# WL-ATT.net
KiCad netlist of a schematic drawn in Altium Designer
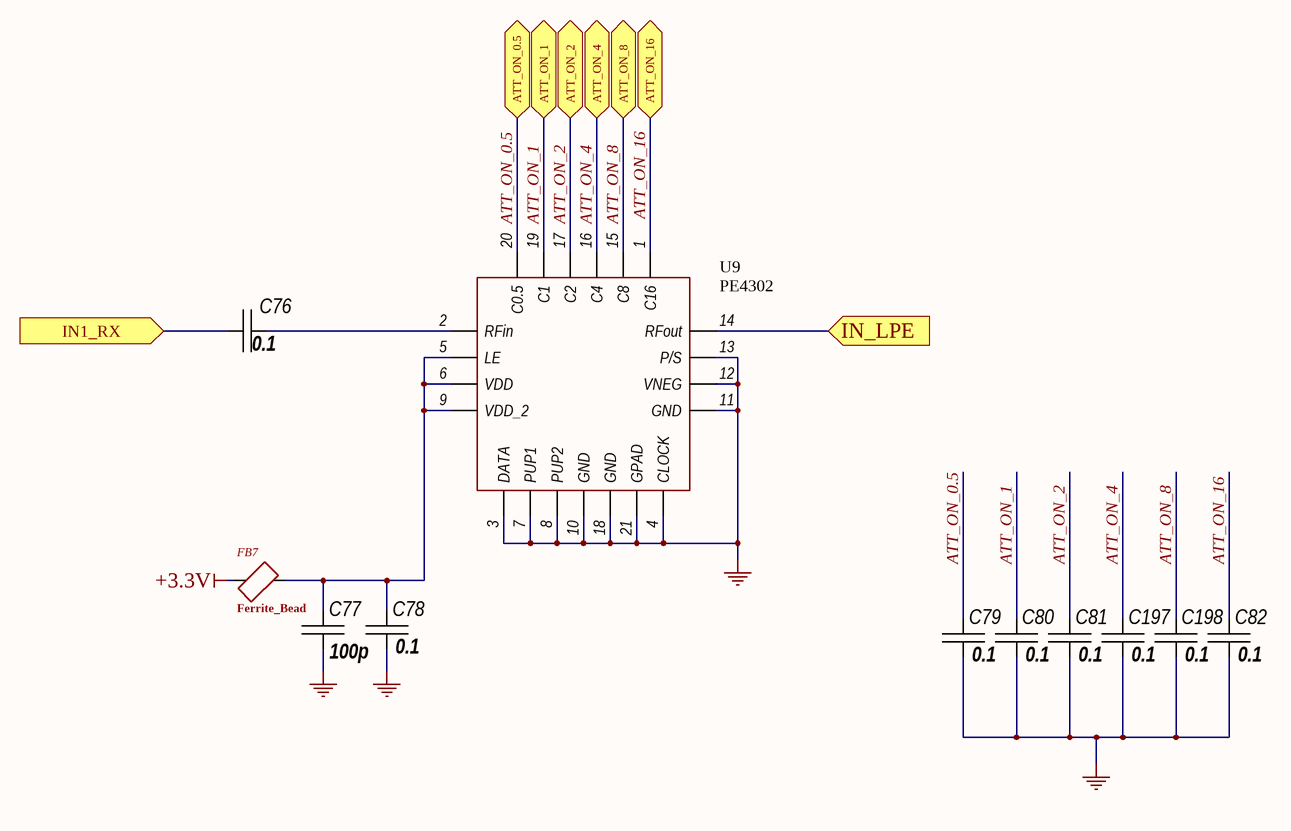
[diagram p0: WL-ATT.SchDoc]

(export (version "E")
  (design (tool "Eeschema 10.0.6"))
  (components
    (comp (ref "C76")
      (value "0.1")
      (footprint "standard:CH0805C")
      (libsource (lib "Discrete") (part "Capacitor"))
    )
    (comp (ref "C77")
      (value "100p")
      (footprint "standard:CH0805C")
      (libsource (lib "Discrete") (part "Capacitor"))
    )
    (comp (ref "C78")
      (value "0.1")
      (footprint "standard:CH0805C")
      (libsource (lib "Discrete") (part "Capacitor"))
    )
    (comp (ref "C79")
      (value "0.1")
      (footprint "standard:CH0805C")
      (libsource (lib "Discrete") (part "Capacitor"))
    )
    (comp (ref "C80")
      (value "0.1")
      (footprint "standard:CH0805C")
      (libsource (lib "Discrete") (part "Capacitor"))
    )
    (comp (ref "C81")
      (value "0.1")
      (footprint "standard:CH0805C")
      (libsource (lib "Discrete") (part "Capacitor"))
    )
    (comp (ref "C82")
      (value "0.1")
      (footprint "standard:CH0805C")
      (libsource (lib "Discrete") (part "Capacitor"))
    )
    (comp (ref "C197")
      (value "0.1")
      (footprint "standard:CH0805C")
      (libsource (lib "Discrete") (part "Capacitor"))
    )
    (comp (ref "C198")
      (value "0.1")
      (footprint "standard:CH0805C")
      (libsource (lib "Discrete") (part "Capacitor"))
    )
    (comp (ref "FB7") (value "Ferrite_Bead") (footprint "CH0805L") (libsource (lib "Discrete") (part "FB")))
    (comp (ref "U9") (value "PE4302") (footprint "20-QFN (4x4)") (libsource (lib "Digital") (part "PE4302")))
  )
  (nets
    (net (code "1") (name "+3.3V") (class "Default")
      (node (ref "FB7") (pin "2") (pinfunction "2_2") (pintype "passive"))
    )
    (net (code "2") (name "/ATT_ON_0.5") (class "Default")
      (node (ref "C79") (pin "2") (pinfunction "2_2") (pintype "power_in"))
      (node (ref "U9") (pin "20") (pinfunction "C0.5_20") (pintype "passive"))
    )
    (net (code "3") (name "/ATT_ON_1") (class "Default")
      (node (ref "C80") (pin "2") (pinfunction "2_2") (pintype "power_in"))
      (node (ref "U9") (pin "19") (pinfunction "C1_19") (pintype "passive"))
    )
    (net (code "4") (name "/ATT_ON_2") (class "Default")
      (node (ref "C81") (pin "2") (pinfunction "2_2") (pintype "power_in"))
      (node (ref "U9") (pin "17") (pinfunction "C2_17") (pintype "passive"))
    )
    (net (code "5") (name "/ATT_ON_4") (class "Default")
      (node (ref "C197") (pin "2") (pinfunction "2_2") (pintype "power_in"))
      (node (ref "U9") (pin "16") (pinfunction "C4_16") (pintype "passive"))
    )
    (net (code "6") (name "/ATT_ON_8") (class "Default")
      (node (ref "C198") (pin "2") (pinfunction "2_2") (pintype "power_in"))
      (node (ref "U9") (pin "15") (pinfunction "C8_15") (pintype "passive"))
    )
    (net (code "7") (name "/ATT_ON_16") (class "Default")
      (node (ref "C82") (pin "2") (pinfunction "2_2") (pintype "power_in"))
      (node (ref "U9") (pin "1") (pinfunction "C16_1") (pintype "passive"))
    )
    (net (code "8") (name "/IN1_RX") (class "Default")
      (node (ref "C76") (pin "1") (pinfunction "1_1") (pintype "power_in"))
    )
    (net (code "9") (name "/IN_LPE") (class "Default")
      (node (ref "U9") (pin "14") (pinfunction "RFout_14") (pintype "passive"))
    )
    (net (code "10") (name "GND") (class "Default")
      (node (ref "C197") (pin "1") (pinfunction "1_1") (pintype "power_in"))
      (node (ref "C198") (pin "1") (pinfunction "1_1") (pintype "power_in"))
      (node (ref "C77") (pin "1") (pinfunction "1_1") (pintype "power_in"))
      (node (ref "C78") (pin "1") (pinfunction "1_1") (pintype "power_in"))
      (node (ref "C79") (pin "1") (pinfunction "1_1") (pintype "power_in"))
      (node (ref "C80") (pin "1") (pinfunction "1_1") (pintype "power_in"))
      (node (ref "C81") (pin "1") (pinfunction "1_1") (pintype "power_in"))
      (node (ref "C82") (pin "1") (pinfunction "1_1") (pintype "power_in"))
      (node (ref "U9") (pin "10") (pinfunction "GND_10") (pintype "passive"))
      (node (ref "U9") (pin "11") (pinfunction "GND_11") (pintype "passive"))
      (node (ref "U9") (pin "12") (pinfunction "VNEG_12") (pintype "passive"))
      (node (ref "U9") (pin "13") (pinfunction "P/S_13") (pintype "passive"))
      (node (ref "U9") (pin "18") (pinfunction "GND_18") (pintype "passive"))
      (node (ref "U9") (pin "21") (pinfunction "GPAD_21") (pintype "passive"))
      (node (ref "U9") (pin "3") (pinfunction "DATA_3") (pintype "passive"))
      (node (ref "U9") (pin "4") (pinfunction "CLOCK_4") (pintype "passive"))
      (node (ref "U9") (pin "7") (pinfunction "PUP1_7") (pintype "passive"))
      (node (ref "U9") (pin "8") (pinfunction "PUP2_8") (pintype "passive"))
    )
    (net (code "11") (name "Net-(U9-LE)") (class "Default")
      (node (ref "C77") (pin "2") (pinfunction "2_2") (pintype "power_in"))
      (node (ref "C78") (pin "2") (pinfunction "2_2") (pintype "power_in"))
      (node (ref "FB7") (pin "1") (pinfunction "1_1") (pintype "passive"))
      (node (ref "U9") (pin "5") (pinfunction "LE_5") (pintype "passive"))
      (node (ref "U9") (pin "6") (pinfunction "VDD_6") (pintype "passive"))
      (node (ref "U9") (pin "9") (pinfunction "VDD_2_9") (pintype "passive"))
    )
    (net (code "12") (name "Net-(U9-RFin)") (class "Default")
      (node (ref "C76") (pin "2") (pinfunction "2_2") (pintype "power_in"))
      (node (ref "U9") (pin "2") (pinfunction "RFin_2") (pintype "passive"))
    )
  )
)
